# rs323-ttl-hack.net
KiCad netlist of a schematic drawn in EAGLE
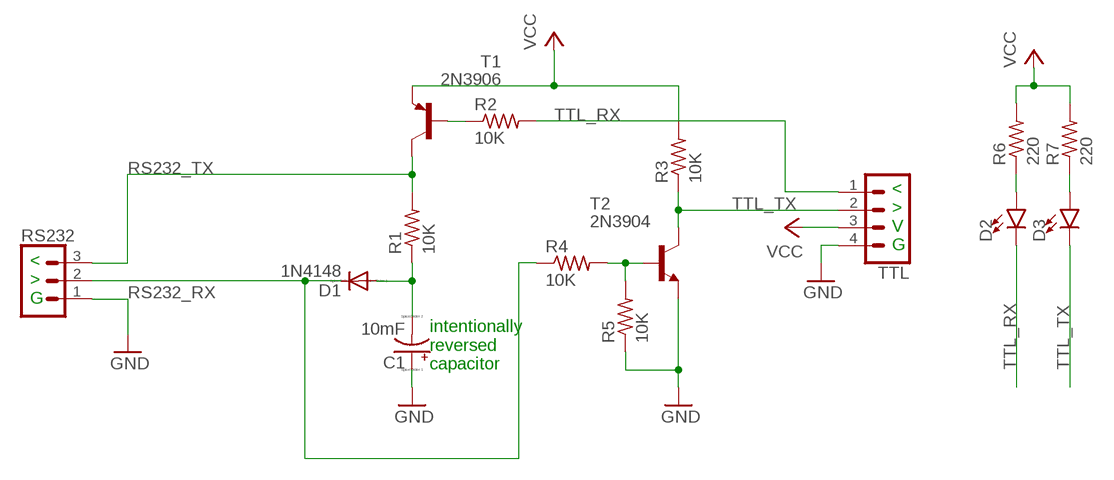
[diagram p0: schematic, sheet 1]

(export (version "E")
  (design (tool "Eeschema 10.0.6"))
  (components
    (comp (ref "C1")
      (value "10mF")
      (footprint "eagle-import:E2,5-6")
      (libsource (lib "eagle-import") (part "CPOL-USE2.5-6"))
    )
    (comp (ref "D1")
      (value "1N4148")
      (footprint "eagle-import:DO35-10")
      (libsource (lib "eagle-import") (part "1N4148DO35-10"))
    )
    (comp (ref "D2")
      (value "LED3MM")
      (footprint "eagle-import:LED_3MM")
      (libsource (lib "eagle-import") (part "LED3MM"))
    )
    (comp (ref "D3")
      (value "LED3MM")
      (footprint "eagle-import:LED_3MM")
      (libsource (lib "eagle-import") (part "LED3MM"))
    )
    (comp (ref "R1")
      (value "10K")
      (footprint "eagle-import:0207_10")
      (libsource (lib "eagle-import") (part "R-US_0207/10"))
    )
    (comp (ref "R2")
      (value "10K")
      (footprint "eagle-import:0207_10")
      (libsource (lib "eagle-import") (part "R-US_0207/10"))
    )
    (comp (ref "R3")
      (value "10K")
      (footprint "eagle-import:0207_10")
      (libsource (lib "eagle-import") (part "R-US_0207/10"))
    )
    (comp (ref "R4")
      (value "10K")
      (footprint "eagle-import:0207_10")
      (libsource (lib "eagle-import") (part "R-US_0207/10"))
    )
    (comp (ref "R5")
      (value "10K")
      (footprint "eagle-import:0207_10")
      (libsource (lib "eagle-import") (part "R-US_0207/10"))
    )
    (comp (ref "R6")
      (value "220")
      (footprint "eagle-import:0207_10")
      (libsource (lib "eagle-import") (part "R-US_0207/10"))
    )
    (comp (ref "R7")
      (value "220")
      (footprint "eagle-import:0207_10")
      (libsource (lib "eagle-import") (part "R-US_0207/10"))
    )
    (comp (ref "RS232")
      (value "CONN_03")
      (footprint "eagle-import:1X03")
      (libsource (lib "eagle-import") (part "CONN_03"))
    )
    (comp (ref "T1")
      (value "2N3906")
      (footprint "eagle-import:TO92-EBC")
      (libsource (lib "eagle-import") (part "-PNP-TO92-EBC2N3906"))
    )
    (comp (ref "T2")
      (value "2N3904")
      (footprint "eagle-import:TO92-EBC")
      (libsource (lib "eagle-import") (part "-NPN-TO92-EBC2N3904"))
    )
    (comp (ref "TTL")
      (value "CONN_04")
      (footprint "eagle-import:1X04")
      (libsource (lib "eagle-import") (part "CONN_04"))
    )
  )
  (nets
    (net (code "1") (name "/RS232_RX") (class "Default")
      (node (ref "D1") (pin "C") (pinfunction "C_C") (pintype "passive"))
      (node (ref "R4") (pin "1") (pinfunction "1_1") (pintype "passive"))
      (node (ref "RS232") (pin "2") (pinfunction "2_2") (pintype "passive"))
    )
    (net (code "2") (name "/RS232_TX") (class "Default")
      (node (ref "R1") (pin "2") (pinfunction "2_2") (pintype "passive"))
      (node (ref "RS232") (pin "3") (pinfunction "3_3") (pintype "passive"))
      (node (ref "T1") (pin "C") (pinfunction "C_C") (pintype "passive"))
    )
    (net (code "3") (name "/TTL_RX") (class "Default")
      (node (ref "D2") (pin "K") (pinfunction "C_K") (pintype "passive"))
      (node (ref "R2") (pin "2") (pinfunction "2_2") (pintype "passive"))
      (node (ref "TTL") (pin "1") (pinfunction "1_1") (pintype "passive"))
    )
    (net (code "4") (name "/TTL_TX") (class "Default")
      (node (ref "D3") (pin "K") (pinfunction "C_K") (pintype "passive"))
      (node (ref "R3") (pin "1") (pinfunction "1_1") (pintype "passive"))
      (node (ref "T2") (pin "C") (pinfunction "C_C") (pintype "passive"))
      (node (ref "TTL") (pin "2") (pinfunction "2_2") (pintype "passive"))
    )
    (net (code "5") (name "GND") (class "Default")
      (node (ref "C1") (pin "+") (pinfunction "+_+") (pintype "passive"))
      (node (ref "R5") (pin "1") (pinfunction "1_1") (pintype "passive"))
      (node (ref "RS232") (pin "1") (pinfunction "1_1") (pintype "passive"))
      (node (ref "T2") (pin "E") (pinfunction "E_E") (pintype "passive"))
      (node (ref "TTL") (pin "4") (pinfunction "4_4") (pintype "passive"))
    )
    (net (code "6") (name "Net-(C1-Pad-)") (class "Default")
      (node (ref "C1") (pin "-") (pinfunction "-_-") (pintype "passive"))
      (node (ref "D1") (pin "A") (pinfunction "A_A") (pintype "passive"))
      (node (ref "R1") (pin "1") (pinfunction "1_1") (pintype "passive"))
    )
    (net (code "7") (name "Net-(D2-PadA)") (class "Default")
      (node (ref "D2") (pin "A") (pinfunction "A_A") (pintype "passive"))
      (node (ref "R6") (pin "1") (pinfunction "1_1") (pintype "passive"))
    )
    (net (code "8") (name "Net-(D3-PadA)") (class "Default")
      (node (ref "D3") (pin "A") (pinfunction "A_A") (pintype "passive"))
      (node (ref "R7") (pin "1") (pinfunction "1_1") (pintype "passive"))
    )
    (net (code "9") (name "Net-(R2-Pad1)") (class "Default")
      (node (ref "R2") (pin "1") (pinfunction "1_1") (pintype "passive"))
      (node (ref "T1") (pin "B") (pinfunction "B_B") (pintype "passive"))
    )
    (net (code "10") (name "Net-(R4-Pad2)") (class "Default")
      (node (ref "R4") (pin "2") (pinfunction "2_2") (pintype "passive"))
      (node (ref "R5") (pin "2") (pinfunction "2_2") (pintype "passive"))
      (node (ref "T2") (pin "B") (pinfunction "B_B") (pintype "passive"))
    )
    (net (code "11") (name "VCC") (class "Default")
      (node (ref "R3") (pin "2") (pinfunction "2_2") (pintype "passive"))
      (node (ref "R6") (pin "2") (pinfunction "2_2") (pintype "passive"))
      (node (ref "R7") (pin "2") (pinfunction "2_2") (pintype "passive"))
      (node (ref "T1") (pin "E") (pinfunction "E_E") (pintype "passive"))
      (node (ref "TTL") (pin "3") (pinfunction "3_3") (pintype "passive"))
    )
  )
)
